# CLOCK_GENERATOR.net
KiCad netlist of a schematic drawn in Altium Designer
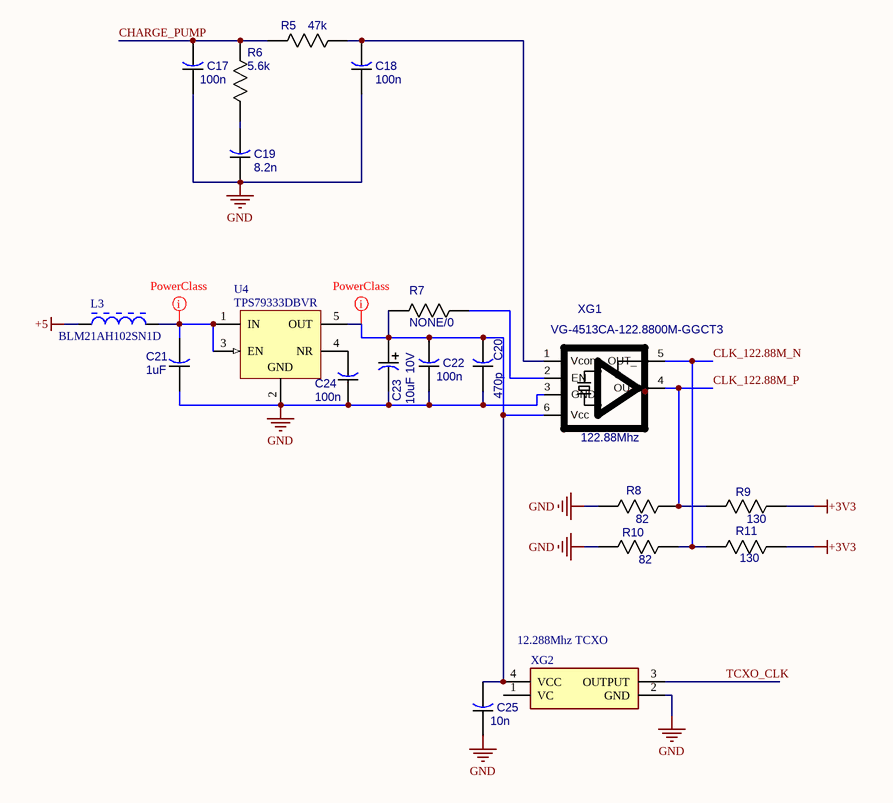
[diagram p0: CLOCK_GENERATOR.SchDoc]

(export (version "E")
  (design (tool "Eeschema 10.0.6"))
  (components
    (comp (ref "C17")
      (value "100n")
      (footprint "CAP_0805")
      (description "CAP_0805")
      (libsource (lib "*") (part "CAP_0805"))
    )
    (comp (ref "C18")
      (value "100n")
      (footprint "CAP_0805")
      (description "CAP_0805")
      (libsource (lib "*") (part "CAP_0805"))
    )
    (comp (ref "C19")
      (value "8.2n")
      (footprint "CAP_0805")
      (description "CAP_0805")
      (libsource (lib "*") (part "CAP_0805"))
    )
    (comp (ref "C20")
      (value "470p")
      (footprint "CAP_0805")
      (description "CAP_0805")
      (libsource (lib "*") (part "CAP_0805"))
    )
    (comp (ref "C21")
      (value "1uF")
      (footprint "CAP_0805")
      (description "CAP_0805")
      (libsource (lib "*") (part "CAP_0805"))
    )
    (comp (ref "C22")
      (value "100n")
      (footprint "CAP_0805")
      (description "CAP_0805")
      (libsource (lib "*") (part "CAP_0805"))
    )
    (comp (ref "C23")
      (value "10uF 10V")
      (footprint "CAPAE_4.3x4.3h5.4")
      (description "CAPAE_4.3x4.3h5.4")
      (libsource (lib "*") (part "CAPAE_4.3x4.3h5.4"))
    )
    (comp (ref "C24")
      (value "100n")
      (footprint "CAP_0805")
      (description "CAP_0805")
      (libsource (lib "*") (part "CAP_0805"))
    )
    (comp (ref "C25")
      (value "10n")
      (footprint "CAP_0805")
      (description "CAP_0805")
      (libsource (lib "*") (part "CAP_0805"))
    )
    (comp (ref "L3")
      (value "BLM21AH102SN1D")
      (footprint "INDC2013X105X50NL20T20")
      (description "Chip Bead, 1000 Ohm, +/- 25%, 200 mA, -55 to 85 degC, 2-Pin SMD, RoHS, Tape and Reel")
      (fields (field (name "MANUFACTURER") "Murata") (field (name "TOLERANCE") "25%"))
      (libsource (lib "Altium Content Vault") (part "IND-FB-2"))
    )
    (comp (ref "R5")
      (value "47k")
      (footprint "RES_0805")
      (description "RES_0805")
      (libsource (lib "*") (part "RES_0805"))
    )
    (comp (ref "R6")
      (value "5.6k")
      (footprint "RES_0805")
      (description "RES_0805")
      (libsource (lib "*") (part "RES_0805"))
    )
    (comp (ref "R7")
      (value "NONE/0")
      (footprint "RES_0805")
      (description "By used crystal")
      (fields (field (name "Comment") "0/NONE"))
      (libsource (lib "*") (part "RES_0805"))
    )
    (comp (ref "R8")
      (value "82")
      (footprint "RES_0805")
      (description "RES_0805")
      (libsource (lib "*") (part "RES_0805"))
    )
    (comp (ref "R9")
      (value "130")
      (footprint "RES_0805")
      (description "RES_0805")
      (libsource (lib "*") (part "RES_0805"))
    )
    (comp (ref "R10")
      (value "82")
      (footprint "RES_0805")
      (description "RES_0805")
      (libsource (lib "*") (part "RES_0805"))
    )
    (comp (ref "R11")
      (value "130")
      (footprint "RES_0805")
      (description "RES_0805")
      (libsource (lib "*") (part "RES_0805"))
    )
    (comp (ref "U4")
      (value "TPS79333DBVR")
      (footprint "DBV0005A_L")
      (fields (field (name "MANUFACTURER") "Texas Instruments"))
      (libsource (lib "Altium Content Vault") (part "TI-TPS79NXX-YYSOT5"))
    )
    (comp (ref "XG1")
      (value "VG-4513CA-122.8800M-GGCT3")
      (footprint "NV7050SA")
      (description "NV7050SA VG-4513CA-122.8800M-GGCT3")
      (fields (field (name "ALTIUM_VALUE") "122.88Mhz"))
      (libsource (lib "*") (part "NV7050SA"))
    )
    (comp (ref "XG2")
      (value "12.288Mhz TCXO")
      (footprint "581L200X2ITT")
      (description "Crystal or Oscillator")
      (fields
        (field (name "MANUFACTURER_PART_NUMBER") "581L200X2ITT")
        (field (name "MOUSER PART NUMBER") "774-581L200X2ITT")
      )
      (libsource (lib "MOTHERBOARD") (part "581L200X2ITT"))
    )
  )
  (nets
    (net (code "1") (name "+3V3") (class "Default")
      (node (ref "R11") (pin "1") (pinfunction "1_1") (pintype "passive"))
      (node (ref "R9") (pin "1") (pinfunction "1_1") (pintype "passive"))
    )
    (net (code "2") (name "+5") (class "Default")
      (node (ref "L3") (pin "1") (pinfunction "1_1") (pintype "passive"))
    )
    (net (code "3") (name "/CHARGE_PUMP") (class "Default")
      (node (ref "C17") (pin "2") (pinfunction "2_2") (pintype "passive"))
      (node (ref "R5") (pin "1") (pinfunction "1_1") (pintype "passive"))
      (node (ref "R6") (pin "1") (pinfunction "1_1") (pintype "passive"))
    )
    (net (code "4") (name "/CLK_122.88M_N") (class "Default")
      (node (ref "R10") (pin "1") (pinfunction "1_1") (pintype "passive"))
      (node (ref "R11") (pin "2") (pinfunction "2_2") (pintype "passive"))
      (node (ref "XG1") (pin "5") (pinfunction "OUT__5") (pintype "passive"))
    )
    (net (code "5") (name "/CLK_122.88M_P") (class "Default")
      (node (ref "R8") (pin "1") (pinfunction "1_1") (pintype "passive"))
      (node (ref "R9") (pin "2") (pinfunction "2_2") (pintype "passive"))
      (node (ref "XG1") (pin "4") (pinfunction "OUT_4") (pintype "passive"))
    )
    (net (code "6") (name "/TCXO_CLK") (class "Default")
      (node (ref "XG2") (pin "3") (pinfunction "OUTPUT_3") (pintype "passive"))
    )
    (net (code "7") (name "GND") (class "Default")
      (node (ref "C17") (pin "1") (pinfunction "1_1") (pintype "passive"))
      (node (ref "C18") (pin "1") (pinfunction "1_1") (pintype "passive"))
      (node (ref "C19") (pin "1") (pinfunction "1_1") (pintype "passive"))
      (node (ref "C20") (pin "1") (pinfunction "1_1") (pintype "passive"))
      (node (ref "C21") (pin "1") (pinfunction "1_1") (pintype "passive"))
      (node (ref "C22") (pin "1") (pinfunction "1_1") (pintype "passive"))
      (node (ref "C23") (pin "2") (pinfunction "MINUS_2") (pintype "passive"))
      (node (ref "C24") (pin "1") (pinfunction "1_1") (pintype "passive"))
      (node (ref "C25") (pin "1") (pinfunction "1_1") (pintype "passive"))
      (node (ref "R10") (pin "2") (pinfunction "2_2") (pintype "passive"))
      (node (ref "R8") (pin "2") (pinfunction "2_2") (pintype "passive"))
      (node (ref "U4") (pin "2") (pinfunction "GND_2") (pintype "power_in"))
      (node (ref "XG1") (pin "3") (pinfunction "GND_3") (pintype "passive"))
      (node (ref "XG2") (pin "2") (pinfunction "GND_2") (pintype "passive"))
    )
    (net (code "8") (name "Net-(C19-Pad2)") (class "Default")
      (node (ref "C19") (pin "2") (pinfunction "2_2") (pintype "passive"))
      (node (ref "R6") (pin "2") (pinfunction "2_2") (pintype "passive"))
    )
    (net (code "9") (name "Net-(C23-PLUS)") (class "Default")
      (node (ref "C20") (pin "2") (pinfunction "2_2") (pintype "passive"))
      (node (ref "C22") (pin "2") (pinfunction "2_2") (pintype "passive"))
      (node (ref "C23") (pin "1") (pinfunction "PLUS_1") (pintype "passive"))
      (node (ref "C25") (pin "2") (pinfunction "2_2") (pintype "passive"))
      (node (ref "R7") (pin "1") (pinfunction "1_1") (pintype "passive"))
      (node (ref "U4") (pin "5") (pinfunction "OUT_5") (pintype "power_in"))
      (node (ref "XG1") (pin "6") (pinfunction "Vcc_6") (pintype "passive"))
      (node (ref "XG2") (pin "4") (pinfunction "VCC_4") (pintype "passive"))
    )
    (net (code "10") (name "Net-(U4-EN)") (class "Default")
      (node (ref "C21") (pin "2") (pinfunction "2_2") (pintype "passive"))
      (node (ref "L3") (pin "2") (pinfunction "2_2") (pintype "passive"))
      (node (ref "U4") (pin "1") (pinfunction "IN_1") (pintype "power_in"))
      (node (ref "U4") (pin "3") (pinfunction "EN_3") (pintype "input"))
    )
    (net (code "11") (name "Net-(U4-NR)") (class "Default")
      (node (ref "C24") (pin "2") (pinfunction "2_2") (pintype "passive"))
      (node (ref "U4") (pin "4") (pinfunction "NR_4") (pintype "passive"))
    )
    (net (code "12") (name "Net-(XG1-EN)") (class "Default")
      (node (ref "R7") (pin "2") (pinfunction "2_2") (pintype "passive"))
      (node (ref "XG1") (pin "2") (pinfunction "EN_2") (pintype "passive"))
    )
    (net (code "13") (name "Net-(XG1-Vcont)") (class "Default")
      (node (ref "C18") (pin "2") (pinfunction "2_2") (pintype "passive"))
      (node (ref "R5") (pin "2") (pinfunction "2_2") (pintype "passive"))
      (node (ref "XG1") (pin "1") (pinfunction "Vcont_1") (pintype "passive"))
    )
    (net (code "14") (name "unconnected-(XG2-VC-Pad1)") (class "Default")
      (node (ref "XG2") (pin "1") (pinfunction "VC_1") (pintype "passive"))
    )
  )
)
